# main.net
KiCad netlist of a schematic drawn in EAGLE
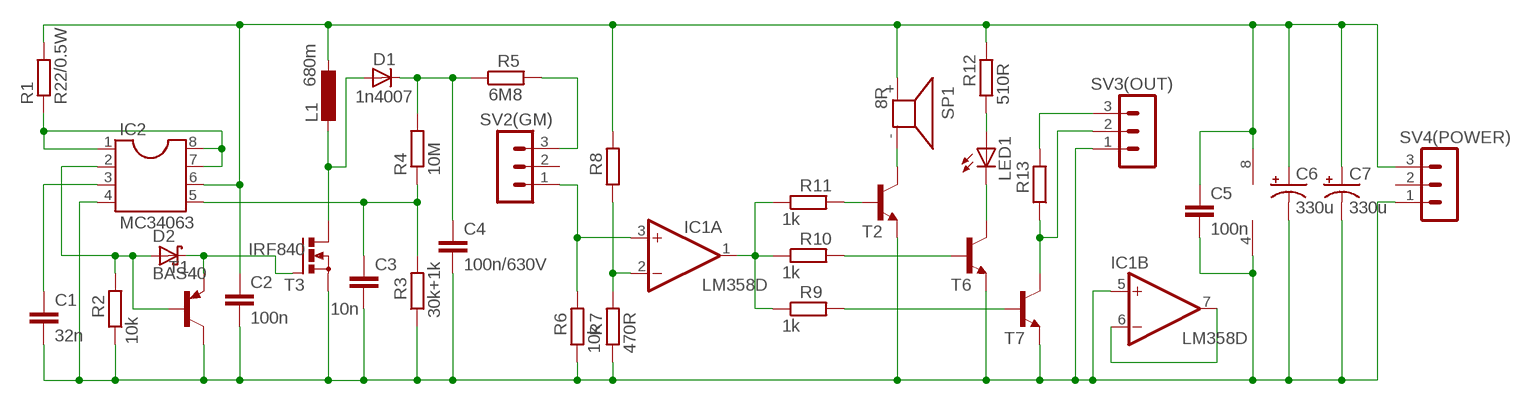
[diagram p0: schematic, sheet 1]

(export (version "E")
  (design (tool "Eeschema 10.0.6"))
  (components
    (comp (ref "C1")
      (value "32n")
      (footprint "eagle-import:C050-025X075")
      (libsource (lib "eagle-import") (part "C-EU050-025X075"))
    )
    (comp (ref "C2")
      (value "100n")
      (footprint "eagle-import:C3216")
      (libsource (lib "eagle-import") (part "C-EUC3216"))
    )
    (comp (ref "C3")
      (value "10n")
      (footprint "eagle-import:C050-025X075")
      (libsource (lib "eagle-import") (part "C-EU050-025X075"))
    )
    (comp (ref "C4")
      (value "100n/630V")
      (footprint "eagle-import:C102-064X133")
      (libsource (lib "eagle-import") (part "C-EU102-064X133"))
    )
    (comp (ref "C5")
      (value "100n")
      (footprint "eagle-import:C3216")
      (libsource (lib "eagle-import") (part "C-EUC3216"))
    )
    (comp (ref "C6")
      (value "330u")
      (footprint "eagle-import:A_3216-18W")
      (libsource (lib "eagle-import") (part "CPOL-USA/3216-18W"))
    )
    (comp (ref "C7")
      (value "330u")
      (footprint "eagle-import:A_3216-18W")
      (libsource (lib "eagle-import") (part "CPOL-USA/3216-18W"))
    )
    (comp (ref "D1")
      (value "1n4007")
      (footprint "eagle-import:DO41-10")
      (libsource (lib "eagle-import") (part "1N4004"))
    )
    (comp (ref "D2")
      (value "BAS40")
      (footprint "eagle-import:SOT23")
      (libsource (lib "eagle-import") (part "BAS40"))
    )
    (comp (ref "IC1")
      (value "LM358D")
      (footprint "eagle-import:SO08")
      (libsource (lib "eagle-import") (part "LM358D"))
    )
    (comp (ref "IC2")
      (value "MC34063")
      (footprint "eagle-import:DIL08")
      (libsource (lib "eagle-import") (part "DIL8"))
    )
    (comp (ref "L1")
      (value "680m")
      (footprint "eagle-import:0207_5V")
      (libsource (lib "eagle-import") (part "L-EU0207/5V"))
    )
    (comp (ref "LED1")
      (value "LEDSFH482")
      (footprint "eagle-import:SFH482")
      (libsource (lib "eagle-import") (part "LEDSFH482"))
    )
    (comp (ref "R1")
      (value "R22/0.5W")
      (footprint "eagle-import:0207_5V")
      (libsource (lib "eagle-import") (part "R-EU_0207/5V"))
    )
    (comp (ref "R2")
      (value "10k")
      (footprint "eagle-import:R1206")
      (libsource (lib "eagle-import") (part "R-EU_R1206"))
    )
    (comp (ref "R3")
      (value "30k+1k")
      (footprint "eagle-import:0207_5V")
      (libsource (lib "eagle-import") (part "R-EU_0207/5V"))
    )
    (comp (ref "R4")
      (value "10M")
      (footprint "eagle-import:0207_5V")
      (libsource (lib "eagle-import") (part "R-EU_0207/5V"))
    )
    (comp (ref "R5")
      (value "6M8")
      (footprint "eagle-import:0207_12")
      (libsource (lib "eagle-import") (part "R-EU_0207/12"))
    )
    (comp (ref "R6")
      (value "10k")
      (footprint "eagle-import:0207_5V")
      (libsource (lib "eagle-import") (part "R-EU_0207/5V"))
    )
    (comp (ref "R7")
      (value "470R")
      (footprint "eagle-import:0207_5V")
      (libsource (lib "eagle-import") (part "R-EU_0207/5V"))
    )
    (comp (ref "R8")
      (value "R-EU_R1206")
      (footprint "eagle-import:R1206")
      (libsource (lib "eagle-import") (part "R-EU_R1206"))
    )
    (comp (ref "R9")
      (value "1k")
      (footprint "eagle-import:M1206")
      (libsource (lib "eagle-import") (part "R-EU_M1206"))
    )
    (comp (ref "R10")
      (value "1k")
      (footprint "eagle-import:M1206")
      (libsource (lib "eagle-import") (part "R-EU_M1206"))
    )
    (comp (ref "R11")
      (value "1k")
      (footprint "eagle-import:M1206")
      (libsource (lib "eagle-import") (part "R-EU_M1206"))
    )
    (comp (ref "R12")
      (value "510R")
      (footprint "eagle-import:M1206")
      (libsource (lib "eagle-import") (part "R-EU_M1206"))
    )
    (comp (ref "R13")
      (value "R-EU_M1206")
      (footprint "eagle-import:M1206")
      (libsource (lib "eagle-import") (part "R-EU_M1206"))
    )
    (comp (ref "SP1")
      (value "8R")
      (footprint "eagle-import:KSS1201")
      (libsource (lib "eagle-import") (part "KSS1201"))
    )
    (comp (ref "SV2(GM)")
      (value "MA03-1")
      (footprint "eagle-import:MA03-1")
      (libsource (lib "eagle-import") (part "MA03-1"))
    )
    (comp (ref "SV3(OUT)")
      (value "MA03-1")
      (footprint "eagle-import:MA03-1")
      (libsource (lib "eagle-import") (part "MA03-1"))
    )
    (comp (ref "SV4(POWER)")
      (value "MA03-1")
      (footprint "eagle-import:MA03-1")
      (libsource (lib "eagle-import") (part "MA03-1"))
    )
    (comp (ref "T1")
      (value "BC807-40-PNP-SOT23-BEC")
      (footprint "eagle-import:SOT23-BEC")
      (libsource (lib "eagle-import") (part "-PNP-SOT23-BECBC807-40"))
    )
    (comp (ref "T2")
      (value "BC848ALT1SMD")
      (footprint "eagle-import:SOT23")
      (libsource (lib "eagle-import") (part "BC848SMDALT1"))
    )
    (comp (ref "T3")
      (value "IRF840")
      (footprint "eagle-import:TO220BV")
      (libsource (lib "eagle-import") (part "BUZ11BV"))
    )
    (comp (ref "T6")
      (value "BC848ALT1SMD")
      (footprint "eagle-import:SOT23")
      (libsource (lib "eagle-import") (part "BC848SMDALT1"))
    )
    (comp (ref "T7")
      (value "BC848ALT1SMD")
      (footprint "eagle-import:SOT23")
      (libsource (lib "eagle-import") (part "BC848SMDALT1"))
    )
  )
  (nets
    (net (code "1") (name "Net-(C1-Pad1)") (class "Default")
      (node (ref "C1") (pin "1") (pinfunction "1_1") (pintype "passive"))
      (node (ref "IC2") (pin "3") (pinfunction "3_3") (pintype "passive"))
    )
    (net (code "2") (name "Net-(C3-Pad1)") (class "Default")
      (node (ref "C3") (pin "1") (pinfunction "1_1") (pintype "passive"))
      (node (ref "IC2") (pin "5") (pinfunction "5_5") (pintype "passive"))
      (node (ref "R3") (pin "2") (pinfunction "2_2") (pintype "passive"))
      (node (ref "R4") (pin "1") (pinfunction "1_1") (pintype "passive"))
    )
    (net (code "3") (name "Net-(C4-Pad1)") (class "Default")
      (node (ref "C4") (pin "1") (pinfunction "1_1") (pintype "passive"))
      (node (ref "D1") (pin "C") (pinfunction "C_C") (pintype "passive"))
      (node (ref "R4") (pin "2") (pinfunction "2_2") (pintype "passive"))
      (node (ref "R5") (pin "1") (pinfunction "1_1") (pintype "passive"))
    )
    (net (code "4") (name "Net-(D1-PadA)") (class "Default")
      (node (ref "D1") (pin "A") (pinfunction "A_A") (pintype "passive"))
      (node (ref "L1") (pin "2") (pinfunction "2_2") (pintype "passive"))
      (node (ref "T3") (pin "D") (pinfunction "D_D") (pintype "passive"))
    )
    (net (code "5") (name "Net-(D2-A)") (class "Default")
      (node (ref "D2") (pin "1") (pinfunction "A_1") (pintype "passive"))
      (node (ref "IC2") (pin "2") (pinfunction "2_2") (pintype "passive"))
      (node (ref "R2") (pin "2") (pinfunction "2_2") (pintype "passive"))
      (node (ref "T1") (pin "B") (pinfunction "B_B") (pintype "passive"))
    )
    (net (code "6") (name "Net-(D2-C)") (class "Default")
      (node (ref "D2") (pin "3") (pinfunction "C_3") (pintype "passive"))
      (node (ref "T1") (pin "E") (pinfunction "E_E") (pintype "passive"))
      (node (ref "T3") (pin "G") (pinfunction "G_G") (pintype "passive"))
    )
    (net (code "7") (name "Net-(IC1A-+IN)") (class "Default")
      (node (ref "IC1") (pin "3") (pinfunction "+IN_3") (pintype "input"))
      (node (ref "R6") (pin "2") (pinfunction "2_2") (pintype "passive"))
      (node (ref "SV2(GM)") (pin "1") (pinfunction "1_1") (pintype "passive"))
    )
    (net (code "8") (name "Net-(IC1A--IN)") (class "Default")
      (node (ref "IC1") (pin "2") (pinfunction "-IN_2") (pintype "input"))
      (node (ref "R7") (pin "2") (pinfunction "2_2") (pintype "passive"))
      (node (ref "R8") (pin "1") (pinfunction "1_1") (pintype "passive"))
    )
    (net (code "9") (name "Net-(IC1A-OUT)") (class "Default")
      (node (ref "IC1") (pin "1") (pinfunction "OUT_1") (pintype "output"))
      (node (ref "R10") (pin "1") (pinfunction "1_1") (pintype "passive"))
      (node (ref "R11") (pin "1") (pinfunction "1_1") (pintype "passive"))
      (node (ref "R9") (pin "1") (pinfunction "1_1") (pintype "passive"))
    )
    (net (code "10") (name "Net-(IC1B-+IN)") (class "Default")
      (node (ref "C1") (pin "2") (pinfunction "2_2") (pintype "passive"))
      (node (ref "C2") (pin "2") (pinfunction "2_2") (pintype "passive"))
      (node (ref "C3") (pin "2") (pinfunction "2_2") (pintype "passive"))
      (node (ref "C4") (pin "2") (pinfunction "2_2") (pintype "passive"))
      (node (ref "C5") (pin "2") (pinfunction "2_2") (pintype "passive"))
      (node (ref "C6") (pin "-") (pinfunction "-_-") (pintype "passive"))
      (node (ref "C7") (pin "-") (pinfunction "-_-") (pintype "passive"))
      (node (ref "IC1") (pin "4") (pinfunction "V-_4") (pintype "power_in"))
      (node (ref "IC1") (pin "5") (pinfunction "+IN_5") (pintype "input"))
      (node (ref "IC2") (pin "4") (pinfunction "4_4") (pintype "passive"))
      (node (ref "R2") (pin "1") (pinfunction "1_1") (pintype "passive"))
      (node (ref "R3") (pin "1") (pinfunction "1_1") (pintype "passive"))
      (node (ref "R6") (pin "1") (pinfunction "1_1") (pintype "passive"))
      (node (ref "R7") (pin "1") (pinfunction "1_1") (pintype "passive"))
      (node (ref "SV3(OUT)") (pin "1") (pinfunction "1_1") (pintype "passive"))
      (node (ref "SV4(POWER)") (pin "1") (pinfunction "1_1") (pintype "passive"))
      (node (ref "T1") (pin "C") (pinfunction "C_C") (pintype "passive"))
      (node (ref "T2") (pin "2") (pinfunction "E_2") (pintype "passive"))
      (node (ref "T3") (pin "S") (pinfunction "S_S") (pintype "passive"))
      (node (ref "T6") (pin "2") (pinfunction "E_2") (pintype "passive"))
      (node (ref "T7") (pin "2") (pinfunction "E_2") (pintype "passive"))
    )
    (net (code "11") (name "Net-(IC1B--IN)") (class "Default")
      (node (ref "IC1") (pin "6") (pinfunction "-IN_6") (pintype "input"))
      (node (ref "IC1") (pin "7") (pinfunction "OUT_7") (pintype "output"))
    )
    (net (code "12") (name "Net-(IC1C-V+)") (class "Default")
      (node (ref "C2") (pin "1") (pinfunction "1_1") (pintype "passive"))
      (node (ref "C5") (pin "1") (pinfunction "1_1") (pintype "passive"))
      (node (ref "C6") (pin "+") (pinfunction "+_+") (pintype "passive"))
      (node (ref "C7") (pin "+") (pinfunction "+_+") (pintype "passive"))
      (node (ref "IC1") (pin "8") (pinfunction "V+_8") (pintype "power_in"))
      (node (ref "IC2") (pin "6") (pinfunction "6_6") (pintype "passive"))
      (node (ref "L1") (pin "1") (pinfunction "1_1") (pintype "passive"))
      (node (ref "R1") (pin "2") (pinfunction "2_2") (pintype "passive"))
      (node (ref "R12") (pin "2") (pinfunction "2_2") (pintype "passive"))
      (node (ref "R8") (pin "2") (pinfunction "2_2") (pintype "passive"))
      (node (ref "SP1") (pin "+") (pinfunction "1_+") (pintype "passive"))
      (node (ref "SV4(POWER)") (pin "3") (pinfunction "3_3") (pintype "passive"))
    )
    (net (code "13") (name "Net-(IC2-Pad1)") (class "Default")
      (node (ref "IC2") (pin "1") (pinfunction "1_1") (pintype "passive"))
      (node (ref "IC2") (pin "7") (pinfunction "7_7") (pintype "passive"))
      (node (ref "IC2") (pin "8") (pinfunction "8_8") (pintype "passive"))
      (node (ref "R1") (pin "1") (pinfunction "1_1") (pintype "passive"))
    )
    (net (code "14") (name "Net-(LED1-C)") (class "Default")
      (node (ref "LED1") (pin "K") (pinfunction "C_K") (pintype "passive"))
      (node (ref "T6") (pin "3") (pinfunction "C_3") (pintype "passive"))
    )
    (net (code "15") (name "Net-(LED1-PadA)") (class "Default")
      (node (ref "LED1") (pin "A") (pinfunction "A_A") (pintype "passive"))
      (node (ref "R12") (pin "1") (pinfunction "1_1") (pintype "passive"))
    )
    (net (code "16") (name "Net-(R5-Pad2)") (class "Default")
      (node (ref "R5") (pin "2") (pinfunction "2_2") (pintype "passive"))
      (node (ref "SV2(GM)") (pin "3") (pinfunction "3_3") (pintype "passive"))
    )
    (net (code "17") (name "Net-(R13-Pad2)") (class "Default")
      (node (ref "R13") (pin "2") (pinfunction "2_2") (pintype "passive"))
      (node (ref "SV3(OUT)") (pin "3") (pinfunction "3_3") (pintype "passive"))
    )
    (net (code "18") (name "Net-(SP1-2)") (class "Default")
      (node (ref "SP1") (pin "-") (pinfunction "2_-") (pintype "passive"))
      (node (ref "T2") (pin "3") (pinfunction "C_3") (pintype "passive"))
    )
    (net (code "19") (name "Net-(T2-B)") (class "Default")
      (node (ref "R11") (pin "2") (pinfunction "2_2") (pintype "passive"))
      (node (ref "T2") (pin "1") (pinfunction "B_1") (pintype "passive"))
    )
    (net (code "20") (name "Net-(T6-B)") (class "Default")
      (node (ref "R10") (pin "2") (pinfunction "2_2") (pintype "passive"))
      (node (ref "T6") (pin "1") (pinfunction "B_1") (pintype "passive"))
    )
    (net (code "21") (name "Net-(T7-B)") (class "Default")
      (node (ref "R9") (pin "2") (pinfunction "2_2") (pintype "passive"))
      (node (ref "T7") (pin "1") (pinfunction "B_1") (pintype "passive"))
    )
    (net (code "22") (name "Net-(T7-C)") (class "Default")
      (node (ref "R13") (pin "1") (pinfunction "1_1") (pintype "passive"))
      (node (ref "SV3(OUT)") (pin "2") (pinfunction "2_2") (pintype "passive"))
      (node (ref "T7") (pin "3") (pinfunction "C_3") (pintype "passive"))
    )
    (net (code "23") (name "unconnected-(SV2(GM)-Pad2)") (class "Default")
      (node (ref "SV2(GM)") (pin "2") (pinfunction "2_2") (pintype "passive"))
    )
    (net (code "24") (name "unconnected-(SV4(POWER)-Pad2)") (class "Default")
      (node (ref "SV4(POWER)") (pin "2") (pinfunction "2_2") (pintype "passive"))
    )
  )
)
